# iceWerx_Carrier_before_Lab_4.net
KiCad netlist of a schematic drawn in EAGLE
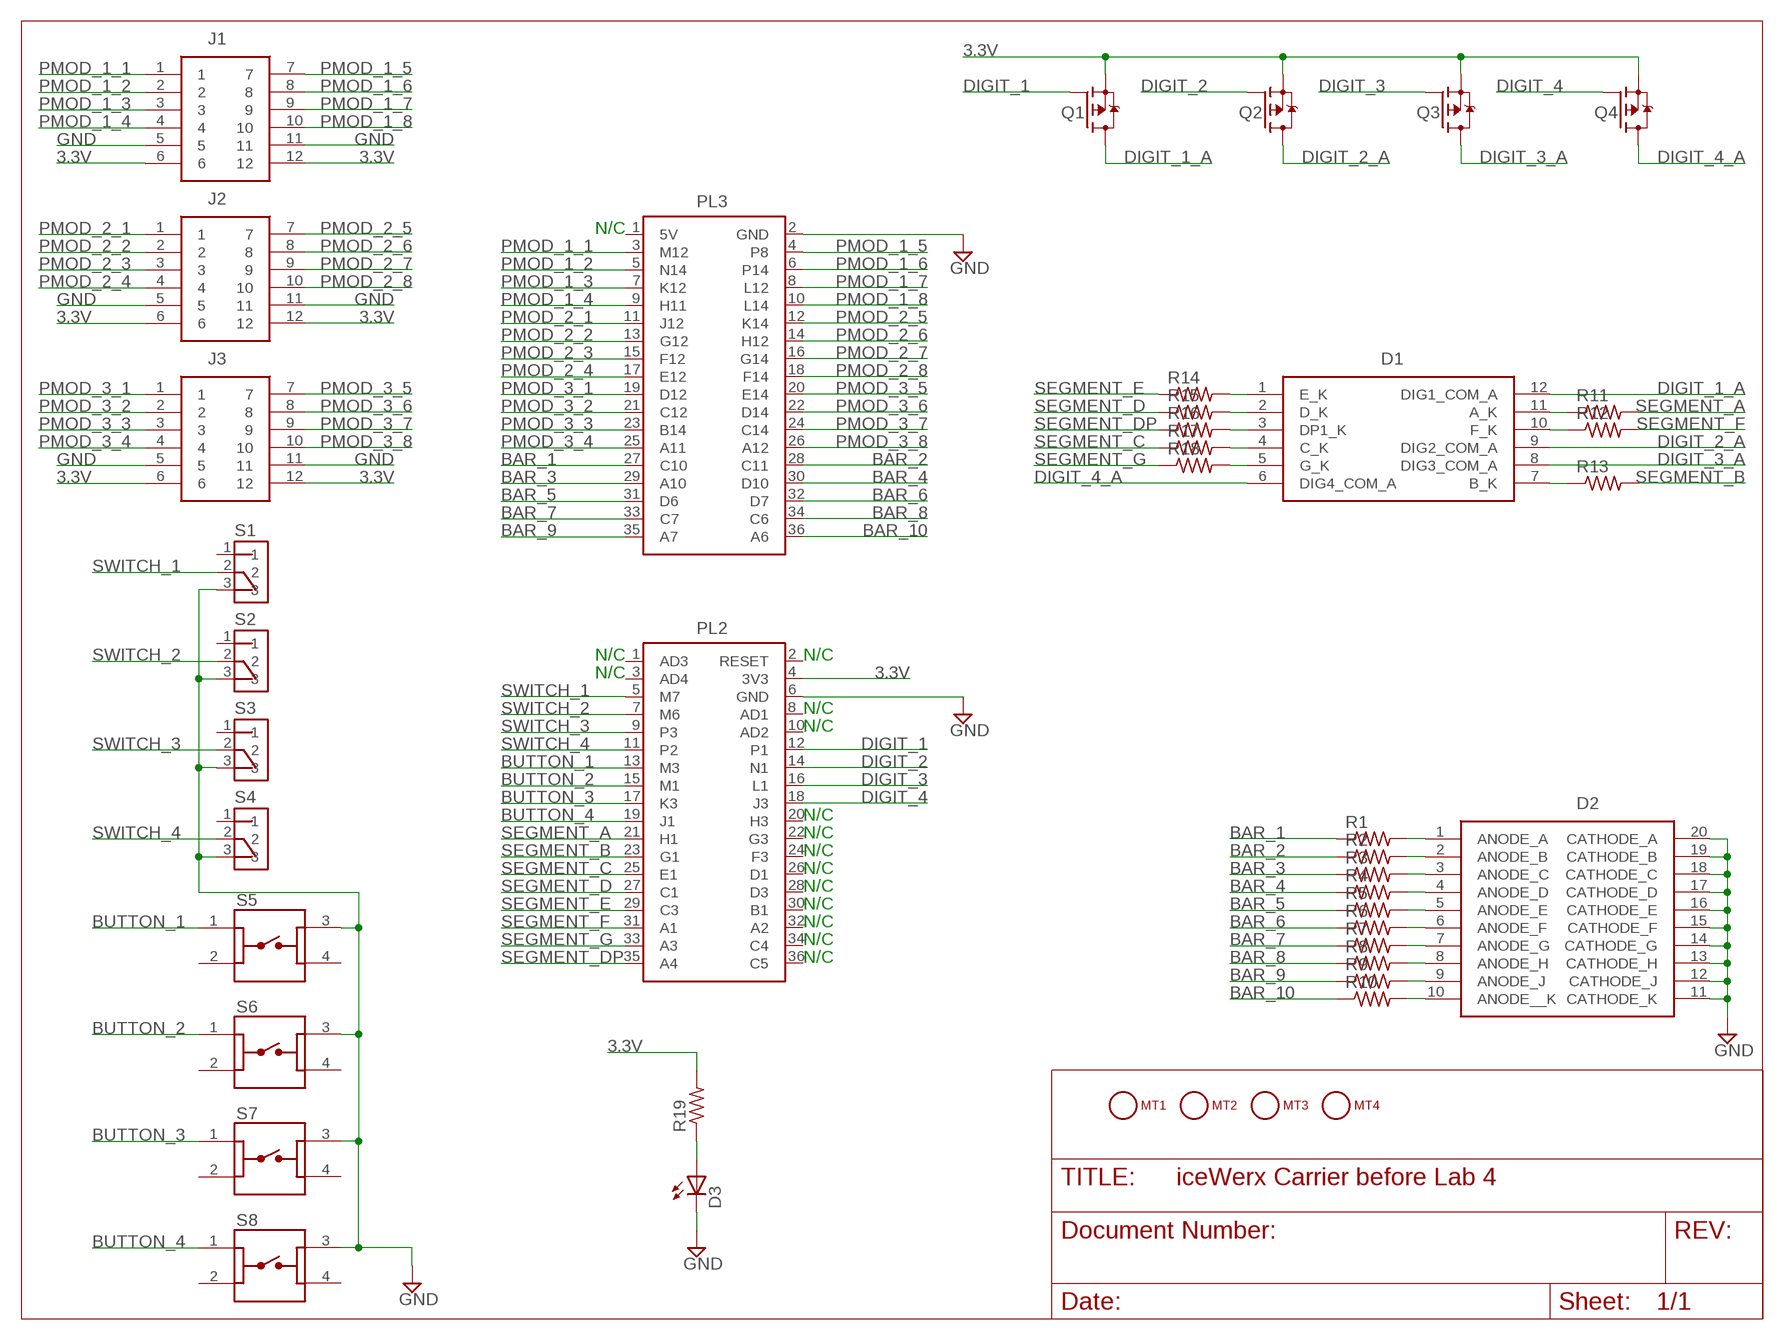
[diagram p0: schematic, sheet 1]

(export (version "E")
  (design (tool "Eeschema 10.0.6"))
  (components
    (comp (ref "D1")
      (value "LDQ-M282RI")
      (footprint "eagle-import:LDQM282RI")
      (fields (field (name "MOUSER_PART_NUMBER") "696-LDQ-M282RI"))
      (libsource (lib "eagle-import") (part "LDQ-M282RI"))
    )
    (comp (ref "D2")
      (value "LTA-1000G")
      (footprint "eagle-import:DIPS762W50P254L2527H825Q20N")
      (fields (field (name "MOUSER_PART_NUMBER") "859-LTA-1000G"))
      (libsource (lib "eagle-import") (part "LTA-1000G"))
    )
    (comp (ref "D3")
      (value "LED5MM")
      (footprint "eagle-import:LED5MM")
      (libsource (lib "eagle-import") (part "LED5MM"))
    )
    (comp (ref "J1")
      (value "PMOD-SOCKET-FOR-HOST-BOARD")
      (footprint "eagle-import:PMOD-SOCKET-FOR-HOST-BOARD")
      (libsource (lib "eagle-import") (part "PMOD-SOCKET-FOR-HOST-BOARD"))
    )
    (comp (ref "J2")
      (value "PMOD-SOCKET-FOR-HOST-BOARD")
      (footprint "eagle-import:PMOD-SOCKET-FOR-HOST-BOARD")
      (libsource (lib "eagle-import") (part "PMOD-SOCKET-FOR-HOST-BOARD"))
    )
    (comp (ref "J3")
      (value "PMOD-SOCKET-FOR-HOST-BOARD")
      (footprint "eagle-import:PMOD-SOCKET-FOR-HOST-BOARD")
      (libsource (lib "eagle-import") (part "PMOD-SOCKET-FOR-HOST-BOARD"))
    )
    (comp (ref "MT1")
      (value "MOUNTING_HOLE-125_250_ROUND")
      (footprint "eagle-import:MT_125_250")
      (libsource (lib "eagle-import") (part "MOUNTING_HOLE-125_250_ROUND"))
    )
    (comp (ref "MT2")
      (value "MOUNTING_HOLE-125_250_ROUND")
      (footprint "eagle-import:MT_125_250")
      (libsource (lib "eagle-import") (part "MOUNTING_HOLE-125_250_ROUND"))
    )
    (comp (ref "MT3")
      (value "MOUNTING_HOLE-125_250_ROUND")
      (footprint "eagle-import:MT_125_250")
      (libsource (lib "eagle-import") (part "MOUNTING_HOLE-125_250_ROUND"))
    )
    (comp (ref "MT4")
      (value "MOUNTING_HOLE-125_250_ROUND")
      (footprint "eagle-import:MT_125_250")
      (libsource (lib "eagle-import") (part "MOUNTING_HOLE-125_250_ROUND"))
    )
    (comp (ref "PL2")
      (value "ICEWERX-PL2")
      (footprint "eagle-import:TE_4-1734506-1")
      (libsource (lib "eagle-import") (part "ICEWERX-PL2"))
    )
    (comp (ref "PL3")
      (value "ICEWERX-PL3")
      (footprint "eagle-import:TE_4-1734506-1")
      (libsource (lib "eagle-import") (part "ICEWERX-PL3"))
    )
    (comp (ref "Q1")
      (value "NX2301P")
      (footprint "eagle-import:SOT95P230X110-3N")
      (fields (field (name "MANUFACTURER") "Nexperia"))
      (libsource (lib "eagle-import") (part "NX2301P"))
    )
    (comp (ref "Q2")
      (value "NX2301P")
      (footprint "eagle-import:SOT95P230X110-3N")
      (fields (field (name "MANUFACTURER") "Nexperia"))
      (libsource (lib "eagle-import") (part "NX2301P"))
    )
    (comp (ref "Q3")
      (value "NX2301P")
      (footprint "eagle-import:SOT95P230X110-3N")
      (fields (field (name "MANUFACTURER") "Nexperia"))
      (libsource (lib "eagle-import") (part "NX2301P"))
    )
    (comp (ref "Q4")
      (value "NX2301P")
      (footprint "eagle-import:SOT95P230X110-3N")
      (fields (field (name "MANUFACTURER") "Nexperia"))
      (libsource (lib "eagle-import") (part "NX2301P"))
    )
    (comp (ref "R1")
      (value "R-US_0204/5")
      (footprint "eagle-import:0204_5")
      (libsource (lib "eagle-import") (part "R-US_0204/5"))
    )
    (comp (ref "R2")
      (value "R-US_0204/5")
      (footprint "eagle-import:0204_5")
      (libsource (lib "eagle-import") (part "R-US_0204/5"))
    )
    (comp (ref "R3")
      (value "R-US_0204/5")
      (footprint "eagle-import:0204_5")
      (libsource (lib "eagle-import") (part "R-US_0204/5"))
    )
    (comp (ref "R4")
      (value "R-US_0204/5")
      (footprint "eagle-import:0204_5")
      (libsource (lib "eagle-import") (part "R-US_0204/5"))
    )
    (comp (ref "R5")
      (value "R-US_0204/5")
      (footprint "eagle-import:0204_5")
      (libsource (lib "eagle-import") (part "R-US_0204/5"))
    )
    (comp (ref "R6")
      (value "R-US_0204/5")
      (footprint "eagle-import:0204_5")
      (libsource (lib "eagle-import") (part "R-US_0204/5"))
    )
    (comp (ref "R7")
      (value "R-US_0204/5")
      (footprint "eagle-import:0204_5")
      (libsource (lib "eagle-import") (part "R-US_0204/5"))
    )
    (comp (ref "R8")
      (value "R-US_0204/5")
      (footprint "eagle-import:0204_5")
      (libsource (lib "eagle-import") (part "R-US_0204/5"))
    )
    (comp (ref "R9")
      (value "R-US_0204/5")
      (footprint "eagle-import:0204_5")
      (libsource (lib "eagle-import") (part "R-US_0204/5"))
    )
    (comp (ref "R10")
      (value "R-US_0204/5")
      (footprint "eagle-import:0204_5")
      (libsource (lib "eagle-import") (part "R-US_0204/5"))
    )
    (comp (ref "R11")
      (value "R-US_0204/5")
      (footprint "eagle-import:0204_5")
      (libsource (lib "eagle-import") (part "R-US_0204/5"))
    )
    (comp (ref "R12")
      (value "R-US_0204/5")
      (footprint "eagle-import:0204_5")
      (libsource (lib "eagle-import") (part "R-US_0204/5"))
    )
    (comp (ref "R13")
      (value "R-US_0204/5")
      (footprint "eagle-import:0204_5")
      (libsource (lib "eagle-import") (part "R-US_0204/5"))
    )
    (comp (ref "R14")
      (value "R-US_0204/5")
      (footprint "eagle-import:0204_5")
      (libsource (lib "eagle-import") (part "R-US_0204/5"))
    )
    (comp (ref "R15")
      (value "R-US_0204/5")
      (footprint "eagle-import:0204_5")
      (libsource (lib "eagle-import") (part "R-US_0204/5"))
    )
    (comp (ref "R16")
      (value "R-US_0204/5")
      (footprint "eagle-import:0204_5")
      (libsource (lib "eagle-import") (part "R-US_0204/5"))
    )
    (comp (ref "R17")
      (value "R-US_0204/5")
      (footprint "eagle-import:0204_5")
      (libsource (lib "eagle-import") (part "R-US_0204/5"))
    )
    (comp (ref "R18")
      (value "R-US_0204/5")
      (footprint "eagle-import:0204_5")
      (libsource (lib "eagle-import") (part "R-US_0204/5"))
    )
    (comp (ref "R19")
      (value "R-US_0204/5")
      (footprint "eagle-import:0204_5")
      (libsource (lib "eagle-import") (part "R-US_0204/5"))
    )
    (comp (ref "S1")
      (value "OS102011MS2QN1")
      (footprint "eagle-import:SW_OS102011MS2QN1")
      (fields (field (name "MANUFACTURER") "C&K"))
      (libsource (lib "eagle-import") (part "OS102011MS2QN1"))
    )
    (comp (ref "S2")
      (value "OS102011MS2QN1")
      (footprint "eagle-import:SW_OS102011MS2QN1")
      (fields (field (name "MANUFACTURER") "C&K"))
      (libsource (lib "eagle-import") (part "OS102011MS2QN1"))
    )
    (comp (ref "S3")
      (value "OS102011MS2QN1")
      (footprint "eagle-import:SW_OS102011MS2QN1")
      (fields (field (name "MANUFACTURER") "C&K"))
      (libsource (lib "eagle-import") (part "OS102011MS2QN1"))
    )
    (comp (ref "S4")
      (value "OS102011MS2QN1")
      (footprint "eagle-import:SW_OS102011MS2QN1")
      (fields (field (name "MANUFACTURER") "C&K"))
      (libsource (lib "eagle-import") (part "OS102011MS2QN1"))
    )
    (comp (ref "S5")
      (value "1825910-7")
      (footprint "eagle-import:SW_1825910-7")
      (fields (field (name "MANUFACTURER") "TE Connectivity"))
      (libsource (lib "eagle-import") (part "1825910-7"))
    )
    (comp (ref "S6")
      (value "1825910-7")
      (footprint "eagle-import:SW_1825910-7")
      (fields (field (name "MANUFACTURER") "TE Connectivity"))
      (libsource (lib "eagle-import") (part "1825910-7"))
    )
    (comp (ref "S7")
      (value "1825910-7")
      (footprint "eagle-import:SW_1825910-7")
      (fields (field (name "MANUFACTURER") "TE Connectivity"))
      (libsource (lib "eagle-import") (part "1825910-7"))
    )
    (comp (ref "S8")
      (value "1825910-7")
      (footprint "eagle-import:SW_1825910-7")
      (fields (field (name "MANUFACTURER") "TE Connectivity"))
      (libsource (lib "eagle-import") (part "1825910-7"))
    )
  )
  (nets
    (net (code "1") (name "/3.3V") (class "Default")
      (node (ref "J1") (pin "12") (pinfunction "12_12") (pintype "bidirectional"))
      (node (ref "J1") (pin "6") (pinfunction "6_6") (pintype "bidirectional"))
      (node (ref "J2") (pin "12") (pinfunction "12_12") (pintype "bidirectional"))
      (node (ref "J2") (pin "6") (pinfunction "6_6") (pintype "bidirectional"))
      (node (ref "J3") (pin "12") (pinfunction "12_12") (pintype "bidirectional"))
      (node (ref "J3") (pin "6") (pinfunction "6_6") (pintype "bidirectional"))
      (node (ref "PL2") (pin "4") (pinfunction "3V3_4") (pintype "bidirectional"))
      (node (ref "Q1") (pin "2") (pinfunction "S_2") (pintype "passive"))
      (node (ref "Q2") (pin "2") (pinfunction "S_2") (pintype "passive"))
      (node (ref "Q3") (pin "2") (pinfunction "S_2") (pintype "passive"))
      (node (ref "Q4") (pin "2") (pinfunction "S_2") (pintype "passive"))
      (node (ref "R19") (pin "2") (pinfunction "2_2") (pintype "passive"))
    )
    (net (code "2") (name "/BAR_1") (class "Default")
      (node (ref "PL3") (pin "27") (pinfunction "C10_27") (pintype "bidirectional"))
      (node (ref "R1") (pin "1") (pinfunction "1_1") (pintype "passive"))
    )
    (net (code "3") (name "/BAR_2") (class "Default")
      (node (ref "PL3") (pin "28") (pinfunction "C11_28") (pintype "bidirectional"))
      (node (ref "R2") (pin "1") (pinfunction "1_1") (pintype "passive"))
    )
    (net (code "4") (name "/BAR_3") (class "Default")
      (node (ref "PL3") (pin "29") (pinfunction "A10_29") (pintype "bidirectional"))
      (node (ref "R3") (pin "1") (pinfunction "1_1") (pintype "passive"))
    )
    (net (code "5") (name "/BAR_4") (class "Default")
      (node (ref "PL3") (pin "30") (pinfunction "D10_30") (pintype "bidirectional"))
      (node (ref "R4") (pin "1") (pinfunction "1_1") (pintype "passive"))
    )
    (net (code "6") (name "/BAR_5") (class "Default")
      (node (ref "PL3") (pin "31") (pinfunction "D6_31") (pintype "bidirectional"))
      (node (ref "R5") (pin "1") (pinfunction "1_1") (pintype "passive"))
    )
    (net (code "7") (name "/BAR_6") (class "Default")
      (node (ref "PL3") (pin "32") (pinfunction "D7_32") (pintype "bidirectional"))
      (node (ref "R6") (pin "1") (pinfunction "1_1") (pintype "passive"))
    )
    (net (code "8") (name "/BAR_7") (class "Default")
      (node (ref "PL3") (pin "33") (pinfunction "C7_33") (pintype "bidirectional"))
      (node (ref "R7") (pin "1") (pinfunction "1_1") (pintype "passive"))
    )
    (net (code "9") (name "/BAR_8") (class "Default")
      (node (ref "PL3") (pin "34") (pinfunction "C6_34") (pintype "bidirectional"))
      (node (ref "R8") (pin "1") (pinfunction "1_1") (pintype "passive"))
    )
    (net (code "10") (name "/BAR_9") (class "Default")
      (node (ref "PL3") (pin "35") (pinfunction "A7_35") (pintype "bidirectional"))
      (node (ref "R9") (pin "1") (pinfunction "1_1") (pintype "passive"))
    )
    (net (code "11") (name "/BAR_10") (class "Default")
      (node (ref "PL3") (pin "36") (pinfunction "A6_36") (pintype "bidirectional"))
      (node (ref "R10") (pin "1") (pinfunction "1_1") (pintype "passive"))
    )
    (net (code "12") (name "/BUTTON_1") (class "Default")
      (node (ref "PL2") (pin "13") (pinfunction "M3_13") (pintype "bidirectional"))
      (node (ref "S5") (pin "1") (pinfunction "1_1") (pintype "passive"))
    )
    (net (code "13") (name "/BUTTON_2") (class "Default")
      (node (ref "PL2") (pin "15") (pinfunction "M1_15") (pintype "bidirectional"))
      (node (ref "S6") (pin "1") (pinfunction "1_1") (pintype "passive"))
    )
    (net (code "14") (name "/BUTTON_3") (class "Default")
      (node (ref "PL2") (pin "17") (pinfunction "K3_17") (pintype "bidirectional"))
      (node (ref "S7") (pin "1") (pinfunction "1_1") (pintype "passive"))
    )
    (net (code "15") (name "/BUTTON_4") (class "Default")
      (node (ref "PL2") (pin "19") (pinfunction "J1_19") (pintype "bidirectional"))
      (node (ref "S8") (pin "1") (pinfunction "1_1") (pintype "passive"))
    )
    (net (code "16") (name "/DIGIT_1") (class "Default")
      (node (ref "PL2") (pin "12") (pinfunction "P1_12") (pintype "bidirectional"))
      (node (ref "Q1") (pin "1") (pinfunction "G_1") (pintype "passive"))
    )
    (net (code "17") (name "/DIGIT_1_A") (class "Default")
      (node (ref "D1") (pin "12") (pinfunction "DIG1_COM_A_12") (pintype "bidirectional"))
      (node (ref "Q1") (pin "3") (pinfunction "D_3") (pintype "passive"))
    )
    (net (code "18") (name "/DIGIT_2") (class "Default")
      (node (ref "PL2") (pin "14") (pinfunction "N1_14") (pintype "bidirectional"))
      (node (ref "Q2") (pin "1") (pinfunction "G_1") (pintype "passive"))
    )
    (net (code "19") (name "/DIGIT_2_A") (class "Default")
      (node (ref "D1") (pin "9") (pinfunction "DIG2_COM_A_9") (pintype "bidirectional"))
      (node (ref "Q2") (pin "3") (pinfunction "D_3") (pintype "passive"))
    )
    (net (code "20") (name "/DIGIT_3") (class "Default")
      (node (ref "PL2") (pin "16") (pinfunction "L1_16") (pintype "bidirectional"))
      (node (ref "Q3") (pin "1") (pinfunction "G_1") (pintype "passive"))
    )
    (net (code "21") (name "/DIGIT_3_A") (class "Default")
      (node (ref "D1") (pin "8") (pinfunction "DIG3_COM_A_8") (pintype "bidirectional"))
      (node (ref "Q3") (pin "3") (pinfunction "D_3") (pintype "passive"))
    )
    (net (code "22") (name "/DIGIT_4") (class "Default")
      (node (ref "PL2") (pin "18") (pinfunction "J3_18") (pintype "bidirectional"))
      (node (ref "Q4") (pin "1") (pinfunction "G_1") (pintype "passive"))
    )
    (net (code "23") (name "/DIGIT_4_A") (class "Default")
      (node (ref "D1") (pin "6") (pinfunction "DIG4_COM_A_6") (pintype "bidirectional"))
      (node (ref "Q4") (pin "3") (pinfunction "D_3") (pintype "passive"))
    )
    (net (code "24") (name "/PMOD_1_1") (class "Default")
      (node (ref "J1") (pin "1") (pinfunction "1_1") (pintype "bidirectional"))
      (node (ref "PL3") (pin "3") (pinfunction "M12_3") (pintype "bidirectional"))
    )
    (net (code "25") (name "/PMOD_1_2") (class "Default")
      (node (ref "J1") (pin "2") (pinfunction "2_2") (pintype "bidirectional"))
      (node (ref "PL3") (pin "5") (pinfunction "N14_5") (pintype "bidirectional"))
    )
    (net (code "26") (name "/PMOD_1_3") (class "Default")
      (node (ref "J1") (pin "3") (pinfunction "3_3") (pintype "bidirectional"))
      (node (ref "PL3") (pin "7") (pinfunction "K12_7") (pintype "bidirectional"))
    )
    (net (code "27") (name "/PMOD_1_4") (class "Default")
      (node (ref "J1") (pin "4") (pinfunction "4_4") (pintype "bidirectional"))
      (node (ref "PL3") (pin "9") (pinfunction "H11_9") (pintype "bidirectional"))
    )
    (net (code "28") (name "/PMOD_1_5") (class "Default")
      (node (ref "J1") (pin "7") (pinfunction "7_7") (pintype "bidirectional"))
      (node (ref "PL3") (pin "4") (pinfunction "P8_4") (pintype "bidirectional"))
    )
    (net (code "29") (name "/PMOD_1_6") (class "Default")
      (node (ref "J1") (pin "8") (pinfunction "8_8") (pintype "bidirectional"))
      (node (ref "PL3") (pin "6") (pinfunction "P14_6") (pintype "bidirectional"))
    )
    (net (code "30") (name "/PMOD_1_7") (class "Default")
      (node (ref "J1") (pin "9") (pinfunction "9_9") (pintype "bidirectional"))
      (node (ref "PL3") (pin "8") (pinfunction "L12_8") (pintype "bidirectional"))
    )
    (net (code "31") (name "/PMOD_1_8") (class "Default")
      (node (ref "J1") (pin "10") (pinfunction "10_10") (pintype "bidirectional"))
      (node (ref "PL3") (pin "10") (pinfunction "L14_10") (pintype "bidirectional"))
    )
    (net (code "32") (name "/PMOD_2_1") (class "Default")
      (node (ref "J2") (pin "1") (pinfunction "1_1") (pintype "bidirectional"))
      (node (ref "PL3") (pin "11") (pinfunction "J12_11") (pintype "bidirectional"))
    )
    (net (code "33") (name "/PMOD_2_2") (class "Default")
      (node (ref "J2") (pin "2") (pinfunction "2_2") (pintype "bidirectional"))
      (node (ref "PL3") (pin "13") (pinfunction "G12_13") (pintype "bidirectional"))
    )
    (net (code "34") (name "/PMOD_2_3") (class "Default")
      (node (ref "J2") (pin "3") (pinfunction "3_3") (pintype "bidirectional"))
      (node (ref "PL3") (pin "15") (pinfunction "F12_15") (pintype "bidirectional"))
    )
    (net (code "35") (name "/PMOD_2_4") (class "Default")
      (node (ref "J2") (pin "4") (pinfunction "4_4") (pintype "bidirectional"))
      (node (ref "PL3") (pin "17") (pinfunction "E12_17") (pintype "bidirectional"))
    )
    (net (code "36") (name "/PMOD_2_5") (class "Default")
      (node (ref "J2") (pin "7") (pinfunction "7_7") (pintype "bidirectional"))
      (node (ref "PL3") (pin "12") (pinfunction "K14_12") (pintype "bidirectional"))
    )
    (net (code "37") (name "/PMOD_2_6") (class "Default")
      (node (ref "J2") (pin "8") (pinfunction "8_8") (pintype "bidirectional"))
      (node (ref "PL3") (pin "14") (pinfunction "H12_14") (pintype "bidirectional"))
    )
    (net (code "38") (name "/PMOD_2_7") (class "Default")
      (node (ref "J2") (pin "9") (pinfunction "9_9") (pintype "bidirectional"))
      (node (ref "PL3") (pin "16") (pinfunction "G14_16") (pintype "bidirectional"))
    )
    (net (code "39") (name "/PMOD_2_8") (class "Default")
      (node (ref "J2") (pin "10") (pinfunction "10_10") (pintype "bidirectional"))
      (node (ref "PL3") (pin "18") (pinfunction "F14_18") (pintype "bidirectional"))
    )
    (net (code "40") (name "/PMOD_3_1") (class "Default")
      (node (ref "J3") (pin "1") (pinfunction "1_1") (pintype "bidirectional"))
      (node (ref "PL3") (pin "19") (pinfunction "D12_19") (pintype "bidirectional"))
    )
    (net (code "41") (name "/PMOD_3_2") (class "Default")
      (node (ref "J3") (pin "2") (pinfunction "2_2") (pintype "bidirectional"))
      (node (ref "PL3") (pin "21") (pinfunction "C12_21") (pintype "bidirectional"))
    )
    (net (code "42") (name "/PMOD_3_3") (class "Default")
      (node (ref "J3") (pin "3") (pinfunction "3_3") (pintype "bidirectional"))
      (node (ref "PL3") (pin "23") (pinfunction "B14_23") (pintype "bidirectional"))
    )
    (net (code "43") (name "/PMOD_3_4") (class "Default")
      (node (ref "J3") (pin "4") (pinfunction "4_4") (pintype "bidirectional"))
      (node (ref "PL3") (pin "25") (pinfunction "A11_25") (pintype "bidirectional"))
    )
    (net (code "44") (name "/PMOD_3_5") (class "Default")
      (node (ref "J3") (pin "7") (pinfunction "7_7") (pintype "bidirectional"))
      (node (ref "PL3") (pin "20") (pinfunction "E14_20") (pintype "bidirectional"))
    )
    (net (code "45") (name "/PMOD_3_6") (class "Default")
      (node (ref "J3") (pin "8") (pinfunction "8_8") (pintype "bidirectional"))
      (node (ref "PL3") (pin "22") (pinfunction "D14_22") (pintype "bidirectional"))
    )
    (net (code "46") (name "/PMOD_3_7") (class "Default")
      (node (ref "J3") (pin "9") (pinfunction "9_9") (pintype "bidirectional"))
      (node (ref "PL3") (pin "24") (pinfunction "C14_24") (pintype "bidirectional"))
    )
    (net (code "47") (name "/PMOD_3_8") (class "Default")
      (node (ref "J3") (pin "10") (pinfunction "10_10") (pintype "bidirectional"))
      (node (ref "PL3") (pin "26") (pinfunction "A12_26") (pintype "bidirectional"))
    )
    (net (code "48") (name "/SEGMENT_A") (class "Default")
      (node (ref "PL2") (pin "21") (pinfunction "H1_21") (pintype "bidirectional"))
      (node (ref "R11") (pin "2") (pinfunction "2_2") (pintype "passive"))
    )
    (net (code "49") (name "/SEGMENT_B") (class "Default")
      (node (ref "PL2") (pin "23") (pinfunction "G1_23") (pintype "bidirectional"))
      (node (ref "R13") (pin "2") (pinfunction "2_2") (pintype "passive"))
    )
    (net (code "50") (name "/SEGMENT_C") (class "Default")
      (node (ref "PL2") (pin "25") (pinfunction "E1_25") (pintype "bidirectional"))
      (node (ref "R17") (pin "1") (pinfunction "1_1") (pintype "passive"))
    )
    (net (code "51") (name "/SEGMENT_D") (class "Default")
      (node (ref "PL2") (pin "27") (pinfunction "C1_27") (pintype "bidirectional"))
      (node (ref "R15") (pin "1") (pinfunction "1_1") (pintype "passive"))
    )
    (net (code "52") (name "/SEGMENT_DP") (class "Default")
      (node (ref "PL2") (pin "35") (pinfunction "A4_35") (pintype "bidirectional"))
      (node (ref "R16") (pin "1") (pinfunction "1_1") (pintype "passive"))
    )
    (net (code "53") (name "/SEGMENT_E") (class "Default")
      (node (ref "PL2") (pin "29") (pinfunction "C3_29") (pintype "bidirectional"))
      (node (ref "R14") (pin "1") (pinfunction "1_1") (pintype "passive"))
    )
    (net (code "54") (name "/SEGMENT_F") (class "Default")
      (node (ref "PL2") (pin "31") (pinfunction "A1_31") (pintype "bidirectional"))
      (node (ref "R12") (pin "2") (pinfunction "2_2") (pintype "passive"))
    )
    (net (code "55") (name "/SEGMENT_G") (class "Default")
      (node (ref "PL2") (pin "33") (pinfunction "A3_33") (pintype "bidirectional"))
      (node (ref "R18") (pin "1") (pinfunction "1_1") (pintype "passive"))
    )
    (net (code "56") (name "/SWITCH_1") (class "Default")
      (node (ref "PL2") (pin "5") (pinfunction "M7_5") (pintype "bidirectional"))
      (node (ref "S1") (pin "2") (pinfunction "2_2") (pintype "passive"))
    )
    (net (code "57") (name "/SWITCH_2") (class "Default")
      (node (ref "PL2") (pin "7") (pinfunction "M6_7") (pintype "bidirectional"))
      (node (ref "S2") (pin "2") (pinfunction "2_2") (pintype "passive"))
    )
    (net (code "58") (name "/SWITCH_3") (class "Default")
      (node (ref "PL2") (pin "9") (pinfunction "P3_9") (pintype "bidirectional"))
      (node (ref "S3") (pin "2") (pinfunction "2_2") (pintype "passive"))
    )
    (net (code "59") (name "/SWITCH_4") (class "Default")
      (node (ref "PL2") (pin "11") (pinfunction "P2_11") (pintype "bidirectional"))
      (node (ref "S4") (pin "2") (pinfunction "2_2") (pintype "passive"))
    )
    (net (code "60") (name "GND") (class "Default")
      (node (ref "D2") (pin "11") (pinfunction "CATHODE_K_11") (pintype "bidirectional"))
      (node (ref "D2") (pin "12") (pinfunction "CATHODE_J_12") (pintype "bidirectional"))
      (node (ref "D2") (pin "13") (pinfunction "CATHODE_H_13") (pintype "bidirectional"))
      (node (ref "D2") (pin "14") (pinfunction "CATHODE_G_14") (pintype "bidirectional"))
      (node (ref "D2") (pin "15") (pinfunction "CATHODE_F_15") (pintype "bidirectional"))
      (node (ref "D2") (pin "16") (pinfunction "CATHODE_E_16") (pintype "bidirectional"))
      (node (ref "D2") (pin "17") (pinfunction "CATHODE_D_17") (pintype "bidirectional"))
      (node (ref "D2") (pin "18") (pinfunction "CATHODE_C_18") (pintype "bidirectional"))
      (node (ref "D2") (pin "19") (pinfunction "CATHODE_B_19") (pintype "bidirectional"))
      (node (ref "D2") (pin "20") (pinfunction "CATHODE_A_20") (pintype "bidirectional"))
      (node (ref "D3") (pin "K") (pinfunction "C_K") (pintype "passive"))
      (node (ref "J1") (pin "11") (pinfunction "11_11") (pintype "bidirectional"))
      (node (ref "J1") (pin "5") (pinfunction "5_5") (pintype "bidirectional"))
      (node (ref "J2") (pin "11") (pinfunction "11_11") (pintype "bidirectional"))
      (node (ref "J2") (pin "5") (pinfunction "5_5") (pintype "bidirectional"))
      (node (ref "J3") (pin "11") (pinfunction "11_11") (pintype "bidirectional"))
      (node (ref "J3") (pin "5") (pinfunction "5_5") (pintype "bidirectional"))
      (node (ref "PL2") (pin "6") (pinfunction "GND_6") (pintype "bidirectional"))
      (node (ref "PL3") (pin "2") (pinfunction "GND_2") (pintype "bidirectional"))
      (node (ref "S1") (pin "3") (pinfunction "3_3") (pintype "passive"))
      (node (ref "S2") (pin "3") (pinfunction "3_3") (pintype "passive"))
      (node (ref "S3") (pin "3") (pinfunction "3_3") (pintype "passive"))
      (node (ref "S4") (pin "3") (pinfunction "3_3") (pintype "passive"))
      (node (ref "S5") (pin "3") (pinfunction "3_3") (pintype "passive"))
      (node (ref "S6") (pin "3") (pinfunction "3_3") (pintype "passive"))
      (node (ref "S7") (pin "3") (pinfunction "3_3") (pintype "passive"))
      (node (ref "S8") (pin "3") (pinfunction "3_3") (pintype "passive"))
    )
    (net (code "61") (name "Net-(D1-A_K)") (class "Default")
      (node (ref "D1") (pin "11") (pinfunction "A_K_11") (pintype "bidirectional"))
      (node (ref "R11") (pin "1") (pinfunction "1_1") (pintype "passive"))
    )
    (net (code "62") (name "Net-(D1-B_K)") (class "Default")
      (node (ref "D1") (pin "7") (pinfunction "B_K_7") (pintype "bidirectional"))
      (node (ref "R13") (pin "1") (pinfunction "1_1") (pintype "passive"))
    )
    (net (code "63") (name "Net-(D1-C_K)") (class "Default")
      (node (ref "D1") (pin "4") (pinfunction "C_K_4") (pintype "bidirectional"))
      (node (ref "R17") (pin "2") (pinfunction "2_2") (pintype "passive"))
    )
    (net (code "64") (name "Net-(D1-DP1_K)") (class "Default")
      (node (ref "D1") (pin "3") (pinfunction "DP1_K_3") (pintype "bidirectional"))
      (node (ref "R16") (pin "2") (pinfunction "2_2") (pintype "passive"))
    )
    (net (code "65") (name "Net-(D1-D_K)") (class "Default")
      (node (ref "D1") (pin "2") (pinfunction "D_K_2") (pintype "bidirectional"))
      (node (ref "R15") (pin "2") (pinfunction "2_2") (pintype "passive"))
    )
    (net (code "66") (name "Net-(D1-E_K)") (class "Default")
      (node (ref "D1") (pin "1") (pinfunction "E_K_1") (pintype "bidirectional"))
      (node (ref "R14") (pin "2") (pinfunction "2_2") (pintype "passive"))
    )
    (net (code "67") (name "Net-(D1-F_K)") (class "Default")
      (node (ref "D1") (pin "10") (pinfunction "F_K_10") (pintype "bidirectional"))
      (node (ref "R12") (pin "1") (pinfunction "1_1") (pintype "passive"))
    )
    (net (code "68") (name "Net-(D1-G_K)") (class "Default")
      (node (ref "D1") (pin "5") (pinfunction "G_K_5") (pintype "bidirectional"))
      (node (ref "R18") (pin "2") (pinfunction "2_2") (pintype "passive"))
    )
    (net (code "69") (name "Net-(D2-ANODE_A)") (class "Default")
      (node (ref "D2") (pin "1") (pinfunction "ANODE_A_1") (pintype "bidirectional"))
      (node (ref "R1") (pin "2") (pinfunction "2_2") (pintype "passive"))
    )
    (net (code "70") (name "Net-(D2-ANODE_B)") (class "Default")
      (node (ref "D2") (pin "2") (pinfunction "ANODE_B_2") (pintype "bidirectional"))
      (node (ref "R2") (pin "2") (pinfunction "2_2") (pintype "passive"))
    )
    (net (code "71") (name "Net-(D2-ANODE_C)") (class "Default")
      (node (ref "D2") (pin "3") (pinfunction "ANODE_C_3") (pintype "bidirectional"))
      (node (ref "R3") (pin "2") (pinfunction "2_2") (pintype "passive"))
    )
    (net (code "72") (name "Net-(D2-ANODE_D)") (class "Default")
      (node (ref "D2") (pin "4") (pinfunction "ANODE_D_4") (pintype "bidirectional"))
      (node (ref "R4") (pin "2") (pinfunction "2_2") (pintype "passive"))
    )
    (net (code "73") (name "Net-(D2-ANODE_E)") (class "Default")
      (node (ref "D2") (pin "5") (pinfunction "ANODE_E_5") (pintype "bidirectional"))
      (node (ref "R5") (pin "2") (pinfunction "2_2") (pintype "passive"))
    )
    (net (code "74") (name "Net-(D2-ANODE_F)") (class "Default")
      (node (ref "D2") (pin "6") (pinfunction "ANODE_F_6") (pintype "bidirectional"))
      (node (ref "R6") (pin "2") (pinfunction "2_2") (pintype "passive"))
    )
    (net (code "75") (name "Net-(D2-ANODE_G)") (class "Default")
      (node (ref "D2") (pin "7") (pinfunction "ANODE_G_7") (pintype "bidirectional"))
      (node (ref "R7") (pin "2") (pinfunction "2_2") (pintype "passive"))
    )
    (net (code "76") (name "Net-(D2-ANODE_H)") (class "Default")
      (node (ref "D2") (pin "8") (pinfunction "ANODE_H_8") (pintype "bidirectional"))
      (node (ref "R8") (pin "2") (pinfunction "2_2") (pintype "passive"))
    )
    (net (code "77") (name "Net-(D2-ANODE_J)") (class "Default")
      (node (ref "D2") (pin "9") (pinfunction "ANODE_J_9") (pintype "bidirectional"))
      (node (ref "R9") (pin "2") (pinfunction "2_2") (pintype "passive"))
    )
    (net (code "78") (name "Net-(D2-ANODE__K)") (class "Default")
      (node (ref "D2") (pin "10") (pinfunction "ANODE__K_10") (pintype "bidirectional"))
      (node (ref "R10") (pin "2") (pinfunction "2_2") (pintype "passive"))
    )
    (net (code "79") (name "Net-(D3-PadA)") (class "Default")
      (node (ref "D3") (pin "A") (pinfunction "A_A") (pintype "passive"))
      (node (ref "R19") (pin "1") (pinfunction "1_1") (pintype "passive"))
    )
    (net (code "80") (name "unconnected-(MT1-P$1-Pad1)") (class "Default")
      (node (ref "MT1") (pin "1") (pinfunction "P$1_1") (pintype "bidirectional"))
    )
    (net (code "81") (name "unconnected-(MT2-P$1-Pad1)") (class "Default")
      (node (ref "MT2") (pin "1") (pinfunction "P$1_1") (pintype "bidirectional"))
    )
    (net (code "82") (name "unconnected-(MT3-P$1-Pad1)") (class "Default")
      (node (ref "MT3") (pin "1") (pinfunction "P$1_1") (pintype "bidirectional"))
    )
    (net (code "83") (name "unconnected-(MT4-P$1-Pad1)") (class "Default")
      (node (ref "MT4") (pin "1") (pinfunction "P$1_1") (pintype "bidirectional"))
    )
    (net (code "84") (name "unconnected-(PL2-A2-Pad32)") (class "Default")
      (node (ref "PL2") (pin "32") (pinfunction "A2_32") (pintype "bidirectional"))
    )
    (net (code "85") (name "unconnected-(PL2-AD1-Pad8)") (class "Default")
      (node (ref "PL2") (pin "8") (pinfunction "AD1_8") (pintype "bidirectional"))
    )
    (net (code "86") (name "unconnected-(PL2-AD2-Pad10)") (class "Default")
      (node (ref "PL2") (pin "10") (pinfunction "AD2_10") (pintype "bidirectional"))
    )
    (net (code "87") (name "unconnected-(PL2-AD3-Pad1)") (class "Default")
      (node (ref "PL2") (pin "1") (pinfunction "AD3_1") (pintype "bidirectional"))
    )
    (net (code "88") (name "unconnected-(PL2-AD4-Pad3)") (class "Default")
      (node (ref "PL2") (pin "3") (pinfunction "AD4_3") (pintype "bidirectional"))
    )
    (net (code "89") (name "unconnected-(PL2-B1-Pad30)") (class "Default")
      (node (ref "PL2") (pin "30") (pinfunction "B1_30") (pintype "bidirectional"))
    )
    (net (code "90") (name "unconnected-(PL2-C4-Pad34)") (class "Default")
      (node (ref "PL2") (pin "34") (pinfunction "C4_34") (pintype "bidirectional"))
    )
    (net (code "91") (name "unconnected-(PL2-C5-Pad36)") (class "Default")
      (node (ref "PL2") (pin "36") (pinfunction "C5_36") (pintype "bidirectional"))
    )
    (net (code "92") (name "unconnected-(PL2-D1-Pad26)") (class "Default")
      (node (ref "PL2") (pin "26") (pinfunction "D1_26") (pintype "bidirectional"))
    )
    (net (code "93") (name "unconnected-(PL2-D3-Pad28)") (class "Default")
      (node (ref "PL2") (pin "28") (pinfunction "D3_28") (pintype "bidirectional"))
    )
    (net (code "94") (name "unconnected-(PL2-F3-Pad24)") (class "Default")
      (node (ref "PL2") (pin "24") (pinfunction "F3_24") (pintype "bidirectional"))
    )
    (net (code "95") (name "unconnected-(PL2-G3-Pad22)") (class "Default")
      (node (ref "PL2") (pin "22") (pinfunction "G3_22") (pintype "bidirectional"))
    )
    (net (code "96") (name "unconnected-(PL2-H3-Pad20)") (class "Default")
      (node (ref "PL2") (pin "20") (pinfunction "H3_20") (pintype "bidirectional"))
    )
    (net (code "97") (name "unconnected-(PL2-RESET-Pad2)") (class "Default")
      (node (ref "PL2") (pin "2") (pinfunction "RESET_2") (pintype "bidirectional"))
    )
    (net (code "98") (name "unconnected-(PL3-5V-Pad1)") (class "Default")
      (node (ref "PL3") (pin "1") (pinfunction "5V_1") (pintype "bidirectional"))
    )
    (net (code "99") (name "unconnected-(S1-Pad1)") (class "Default")
      (node (ref "S1") (pin "1") (pinfunction "1_1") (pintype "passive"))
    )
    (net (code "100") (name "unconnected-(S2-Pad1)") (class "Default")
      (node (ref "S2") (pin "1") (pinfunction "1_1") (pintype "passive"))
    )
    (net (code "101") (name "unconnected-(S3-Pad1)") (class "Default")
      (node (ref "S3") (pin "1") (pinfunction "1_1") (pintype "passive"))
    )
    (net (code "102") (name "unconnected-(S4-Pad1)") (class "Default")
      (node (ref "S4") (pin "1") (pinfunction "1_1") (pintype "passive"))
    )
    (net (code "103") (name "unconnected-(S5-Pad2)") (class "Default")
      (node (ref "S5") (pin "2") (pinfunction "2_2") (pintype "passive"))
    )
    (net (code "104") (name "unconnected-(S5-Pad4)") (class "Default")
      (node (ref "S5") (pin "4") (pinfunction "4_4") (pintype "passive"))
    )
    (net (code "105") (name "unconnected-(S6-Pad2)") (class "Default")
      (node (ref "S6") (pin "2") (pinfunction "2_2") (pintype "passive"))
    )
    (net (code "106") (name "unconnected-(S6-Pad4)") (class "Default")
      (node (ref "S6") (pin "4") (pinfunction "4_4") (pintype "passive"))
    )
    (net (code "107") (name "unconnected-(S7-Pad2)") (class "Default")
      (node (ref "S7") (pin "2") (pinfunction "2_2") (pintype "passive"))
    )
    (net (code "108") (name "unconnected-(S7-Pad4)") (class "Default")
      (node (ref "S7") (pin "4") (pinfunction "4_4") (pintype "passive"))
    )
    (net (code "109") (name "unconnected-(S8-Pad2)") (class "Default")
      (node (ref "S8") (pin "2") (pinfunction "2_2") (pintype "passive"))
    )
    (net (code "110") (name "unconnected-(S8-Pad4)") (class "Default")
      (node (ref "S8") (pin "4") (pinfunction "4_4") (pintype "passive"))
    )
  )
)
